# Bank_13_Bank_15_Bank_16.net
KiCad netlist of a schematic drawn in Altium Designer
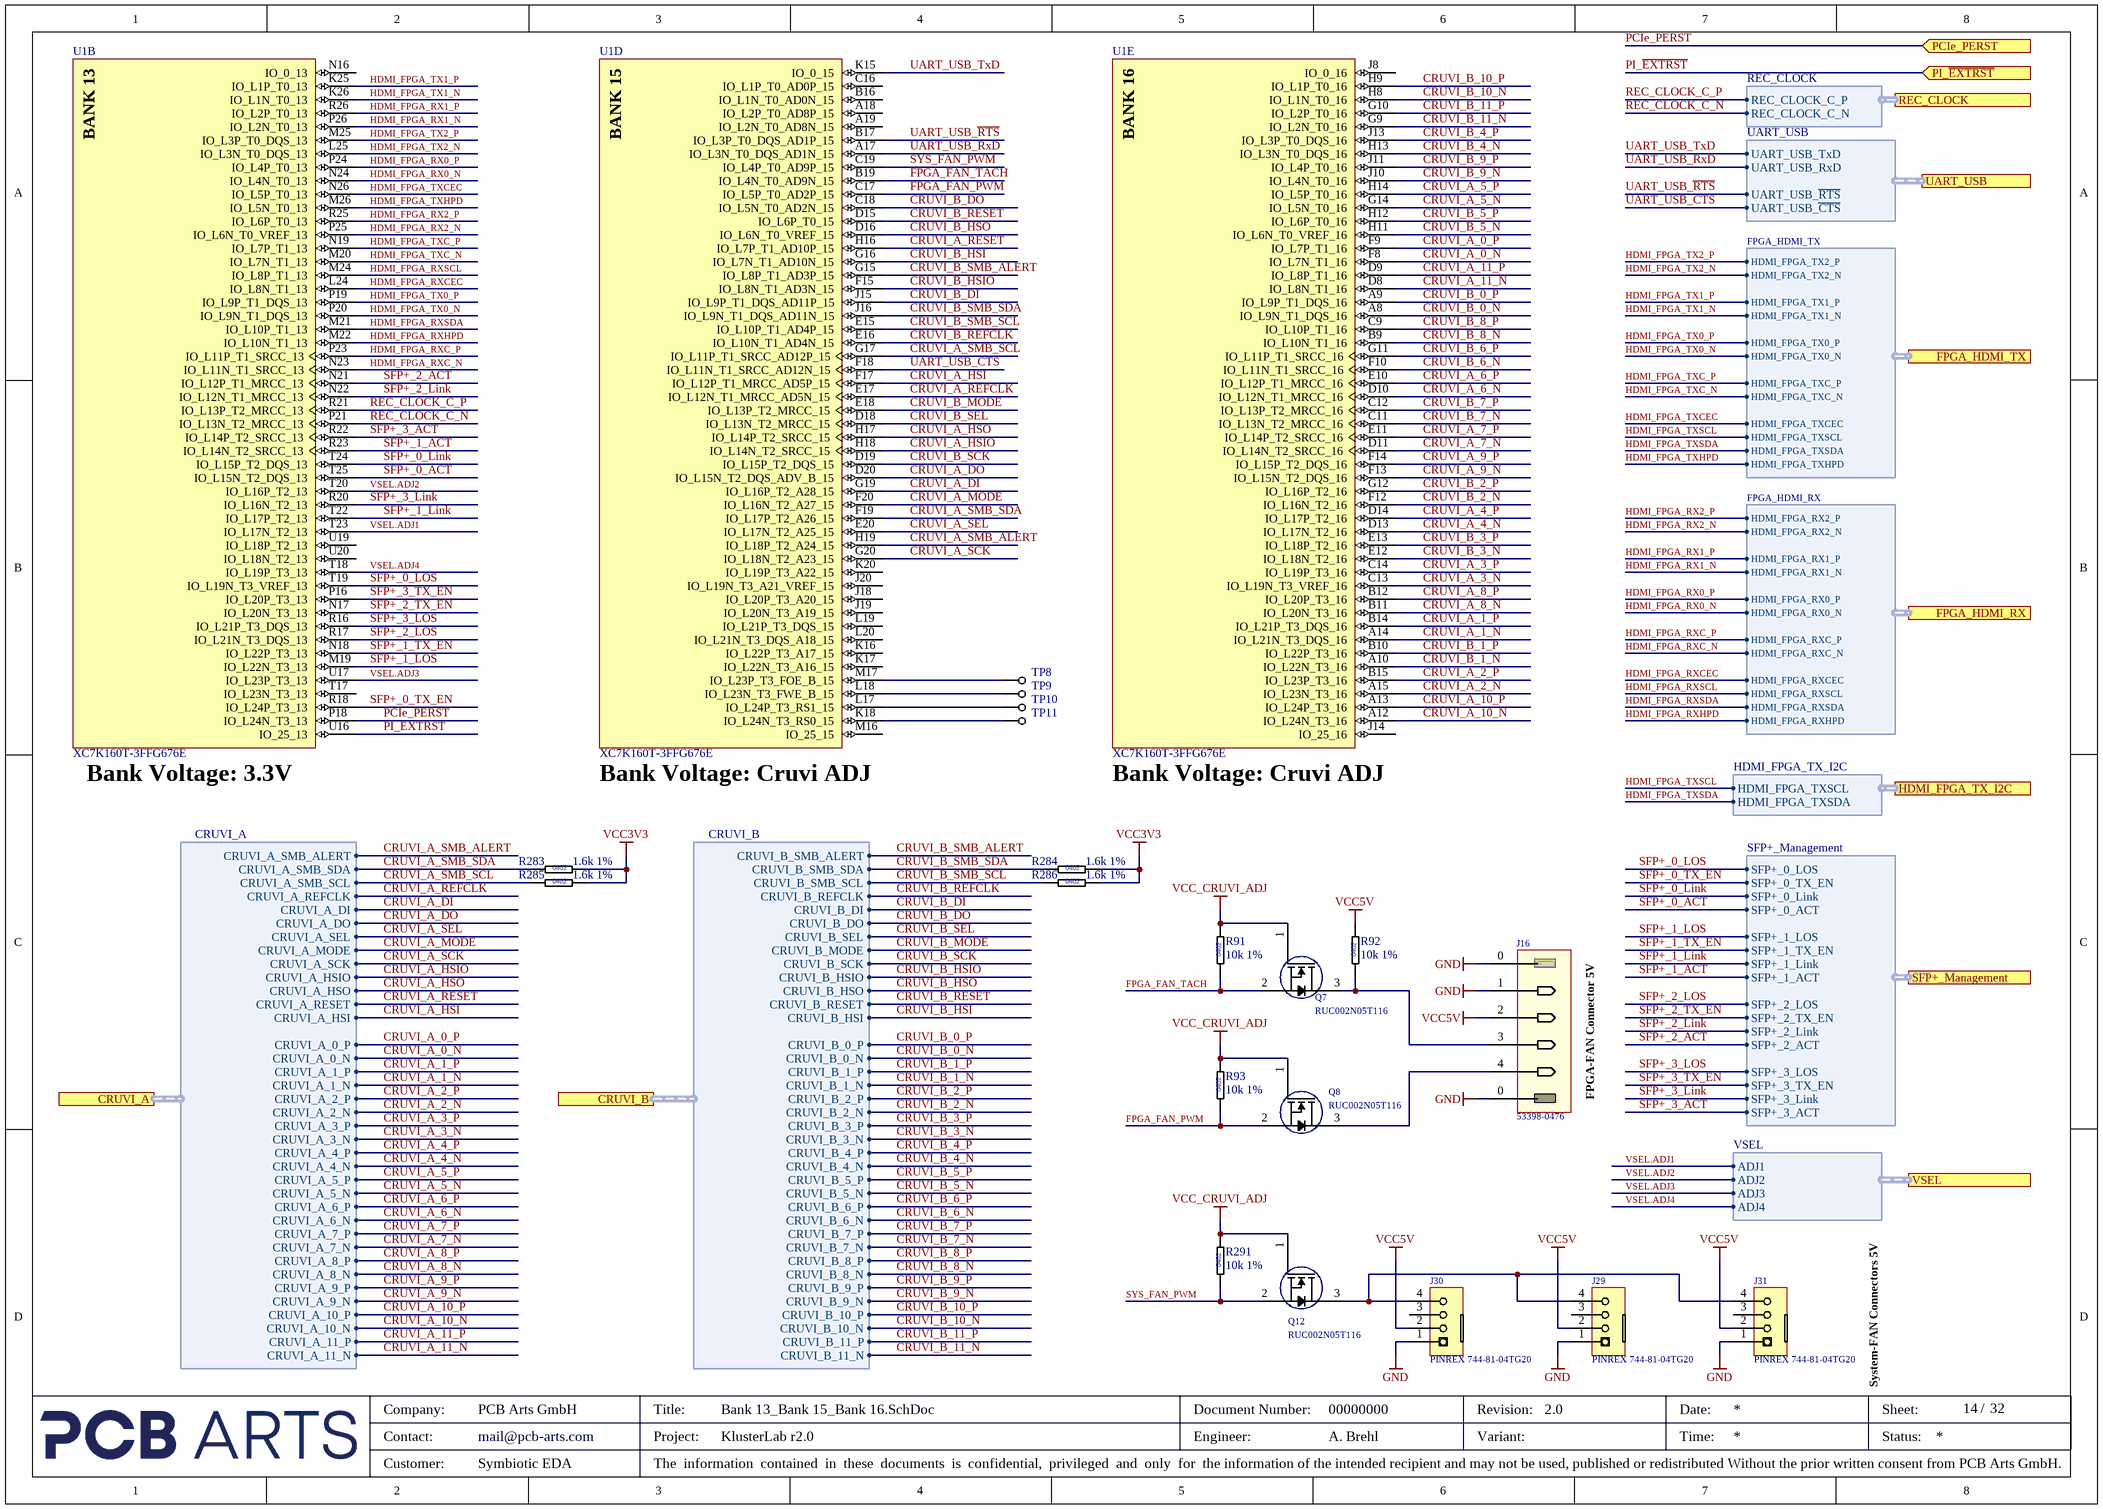
[diagram p0: Bank 13_Bank 15_Bank 16.SchDoc]

(export (version "E")
  (design (tool "Eeschema 10.0.6"))
  (components
    (comp (ref "J16")
      (value "53398-0476")
      (footprint "Conn:Molex 53398-0476")
      (description "1.25mm Pitch, PicoBlade PCB Header, Single Row, horizontal, SMD, 4 Pin")
      (libsource (lib "Conn") (part "53398-0476_1.25mm Pitch, PicoBlade PCB Header, Single Row, horizontal, SMD, 4 Pin"))
    )
    (comp (ref "J29")
      (value "PINREX 744-81-04TG20")
      (footprint "conn:PINREX 744-81-04TG20")
      (description "FAN Connector header 2.54mm 4Pol")
      (libsource (lib "Conn") (part "FAN Connector header 2.54mm 4Pol Pinrex 744-81-04TG20"))
    )
    (comp (ref "J30")
      (value "PINREX 744-81-04TG20")
      (footprint "conn:PINREX 744-81-04TG20")
      (description "FAN Connector header 2.54mm 4Pol")
      (libsource (lib "Conn") (part "FAN Connector header 2.54mm 4Pol Pinrex 744-81-04TG20"))
    )
    (comp (ref "J31")
      (value "PINREX 744-81-04TG20")
      (footprint "conn:PINREX 744-81-04TG20")
      (description "FAN Connector header 2.54mm 4Pol")
      (libsource (lib "Conn") (part "FAN Connector header 2.54mm 4Pol Pinrex 744-81-04TG20"))
    )
    (comp (ref "Q7")
      (value "RUC002N05T116")
      (footprint "trans:SOT95P251X112-3N")
      (description "MOSFET N-Ch 1.2 VGS Spec")
      (libsource (lib "Trans") (part "RUC002N05T116_MOSFET N-Ch 1.2 VGS Spec"))
    )
    (comp (ref "Q8")
      (value "RUC002N05T116")
      (footprint "trans:SOT95P251X112-3N")
      (description "MOSFET N-Ch 1.2 VGS Spec")
      (libsource (lib "Trans") (part "RUC002N05T116_MOSFET N-Ch 1.2 VGS Spec"))
    )
    (comp (ref "Q12")
      (value "RUC002N05T116")
      (footprint "trans:SOT95P251X112-3N")
      (description "MOSFET N-Ch 1.2 VGS Spec")
      (libsource (lib "Trans") (part "RUC002N05T116_MOSFET N-Ch 1.2 VGS Spec"))
    )
    (comp (ref "R91")
      (value "10k 1%")
      (footprint "Res:RES_0402_L")
      (description "Thick Film Resistors - SMD 10kOhm 1%")
      (libsource (lib "Res") (part "RES_0402_10k_1%"))
    )
    (comp (ref "R92")
      (value "10k 1%")
      (footprint "Res:RES_0402_L")
      (description "Thick Film Resistors - SMD 10kOhm 1%")
      (libsource (lib "Res") (part "RES_0402_10k_1%"))
    )
    (comp (ref "R93")
      (value "10k 1%")
      (footprint "Res:RES_0402_L")
      (description "Thick Film Resistors - SMD 10kOhm 1%")
      (libsource (lib "Res") (part "RES_0402_10k_1%"))
    )
    (comp (ref "R283")
      (value "1.6k 1%")
      (footprint "Res:RES_0402_L")
      (description "Thick Film Resistors - SMD 1.6kOhm 1%")
      (libsource (lib "Res") (part "RES_0402_1.6k_1%"))
    )
    (comp (ref "R284")
      (value "1.6k 1%")
      (footprint "Res:RES_0402_L")
      (description "Thick Film Resistors - SMD 1.6kOhm 1%")
      (libsource (lib "Res") (part "RES_0402_1.6k_1%"))
    )
    (comp (ref "R285")
      (value "1.6k 1%")
      (footprint "Res:RES_0402_L")
      (description "Thick Film Resistors - SMD 1.6kOhm 1%")
      (libsource (lib "Res") (part "RES_0402_1.6k_1%"))
    )
    (comp (ref "R286")
      (value "1.6k 1%")
      (footprint "Res:RES_0402_L")
      (description "Thick Film Resistors - SMD 1.6kOhm 1%")
      (libsource (lib "Res") (part "RES_0402_1.6k_1%"))
    )
    (comp (ref "R291")
      (value "10k 1%")
      (footprint "Res:RES_0402_L")
      (description "Thick Film Resistors - SMD 10kOhm 1%")
      (libsource (lib "Res") (part "RES_0402_10k_1%"))
    )
    (comp (ref "TP8")
      (value "Testpoint")
      (footprint "Electro_mech:Testpoint 0.8mm")
      (description "Testpoint 0.8mm")
      (libsource (lib "Electro_Mech") (part "Testpoint 0.8mm"))
    )
    (comp (ref "TP9")
      (value "Testpoint")
      (footprint "Electro_mech:Testpoint 0.8mm")
      (description "Testpoint 0.8mm")
      (libsource (lib "Electro_Mech") (part "Testpoint 0.8mm"))
    )
    (comp (ref "TP10")
      (value "Testpoint")
      (footprint "Electro_mech:Testpoint 0.8mm")
      (description "Testpoint 0.8mm")
      (libsource (lib "Electro_Mech") (part "Testpoint 0.8mm"))
    )
    (comp (ref "TP11")
      (value "Testpoint")
      (footprint "Electro_mech:Testpoint 0.8mm")
      (description "Testpoint 0.8mm")
      (libsource (lib "Electro_Mech") (part "Testpoint 0.8mm"))
    )
    (comp (ref "U1")
      (value "XC7K160T-3FFG676E")
      (footprint "Digital:BGA100P2700X2700X317-676N")
      (description "Kintex-7 FPGA, 400 User I/Os, 8 GTX, 676-Ball BGA, Speed Grade 3, Extended Grade, Pb-Free")
      (libsource (lib "Digital") (part "XC7K160T-3FFG676E_Kintex-7 FPGA, 400 User I/Os, 8 GTX, FFG676"))
    )
  )
  (nets
    (net (code "10") (name "/CRUVI_A_0_N") (class "Default")
      (node (ref "U1") (pin "F8") (pinfunction "IO_L7N_T1_16_F8") (pintype "bidirectional"))
    )
    (net (code "11") (name "/CRUVI_A_0_P") (class "Default")
      (node (ref "U1") (pin "F9") (pinfunction "IO_L7P_T1_16_F9") (pintype "bidirectional"))
    )
    (net (code "12") (name "/CRUVI_A_1_N") (class "Default")
      (node (ref "U1") (pin "A14") (pinfunction "IO_L21N_T3_DQS_16_A14") (pintype "bidirectional"))
    )
    (net (code "13") (name "/CRUVI_A_1_P") (class "Default")
      (node (ref "U1") (pin "B14") (pinfunction "IO_L21P_T3_DQS_16_B14") (pintype "bidirectional"))
    )
    (net (code "14") (name "/CRUVI_A_2_N") (class "Default")
      (node (ref "U1") (pin "A15") (pinfunction "IO_L23N_T3_16_A15") (pintype "bidirectional"))
    )
    (net (code "15") (name "/CRUVI_A_2_P") (class "Default")
      (node (ref "U1") (pin "B15") (pinfunction "IO_L23P_T3_16_B15") (pintype "bidirectional"))
    )
    (net (code "16") (name "/CRUVI_A_3_N") (class "Default")
      (node (ref "U1") (pin "C13") (pinfunction "IO_L19N_T3_VREF_16_C13") (pintype "bidirectional"))
    )
    (net (code "17") (name "/CRUVI_A_3_P") (class "Default")
      (node (ref "U1") (pin "C14") (pinfunction "IO_L19P_T3_16_C14") (pintype "bidirectional"))
    )
    (net (code "18") (name "/CRUVI_A_4_N") (class "Default")
      (node (ref "U1") (pin "D13") (pinfunction "IO_L17N_T2_16_D13") (pintype "bidirectional"))
    )
    (net (code "19") (name "/CRUVI_A_4_P") (class "Default")
      (node (ref "U1") (pin "D14") (pinfunction "IO_L17P_T2_16_D14") (pintype "bidirectional"))
    )
    (net (code "20") (name "/CRUVI_A_5_N") (class "Default")
      (node (ref "U1") (pin "G14") (pinfunction "IO_L5N_T0_16_G14") (pintype "bidirectional"))
    )
    (net (code "21") (name "/CRUVI_A_5_P") (class "Default")
      (node (ref "U1") (pin "H14") (pinfunction "IO_L5P_T0_16_H14") (pintype "bidirectional"))
    )
    (net (code "22") (name "/CRUVI_A_6_N") (class "Default")
      (node (ref "U1") (pin "D10") (pinfunction "IO_L12N_T1_MRCC_16_D10") (pintype "bidirectional"))
    )
    (net (code "23") (name "/CRUVI_A_6_P") (class "Default")
      (node (ref "U1") (pin "E10") (pinfunction "IO_L12P_T1_MRCC_16_E10") (pintype "bidirectional"))
    )
    (net (code "24") (name "/CRUVI_A_7_N") (class "Default")
      (node (ref "U1") (pin "D11") (pinfunction "IO_L14N_T2_SRCC_16_D11") (pintype "bidirectional"))
    )
    (net (code "25") (name "/CRUVI_A_7_P") (class "Default")
      (node (ref "U1") (pin "E11") (pinfunction "IO_L14P_T2_SRCC_16_E11") (pintype "bidirectional"))
    )
    (net (code "26") (name "/CRUVI_A_8_N") (class "Default")
      (node (ref "U1") (pin "B11") (pinfunction "IO_L20N_T3_16_B11") (pintype "bidirectional"))
    )
    (net (code "27") (name "/CRUVI_A_8_P") (class "Default")
      (node (ref "U1") (pin "B12") (pinfunction "IO_L20P_T3_16_B12") (pintype "bidirectional"))
    )
    (net (code "28") (name "/CRUVI_A_9_N") (class "Default")
      (node (ref "U1") (pin "F13") (pinfunction "IO_L15N_T2_DQS_16_F13") (pintype "bidirectional"))
    )
    (net (code "29") (name "/CRUVI_A_9_P") (class "Default")
      (node (ref "U1") (pin "F14") (pinfunction "IO_L15P_T2_DQS_16_F14") (pintype "bidirectional"))
    )
    (net (code "30") (name "/CRUVI_A_10_N") (class "Default")
      (node (ref "U1") (pin "A12") (pinfunction "IO_L24N_T3_16_A12") (pintype "bidirectional"))
    )
    (net (code "31") (name "/CRUVI_A_10_P") (class "Default")
      (node (ref "U1") (pin "A13") (pinfunction "IO_L24P_T3_16_A13") (pintype "bidirectional"))
    )
    (net (code "32") (name "/CRUVI_A_11_N") (class "Default")
      (node (ref "U1") (pin "D8") (pinfunction "IO_L8N_T1_16_D8") (pintype "bidirectional"))
    )
    (net (code "33") (name "/CRUVI_A_11_P") (class "Default")
      (node (ref "U1") (pin "D9") (pinfunction "IO_L8P_T1_16_D9") (pintype "bidirectional"))
    )
    (net (code "34") (name "/CRUVI_A_DI") (class "Default")
      (node (ref "U1") (pin "G19") (pinfunction "IO_L16P_T2_A28_15_G19") (pintype "bidirectional"))
    )
    (net (code "35") (name "/CRUVI_A_DO") (class "Default")
      (node (ref "U1") (pin "D20") (pinfunction "IO_L15N_T2_DQS_ADV_B_15_D20") (pintype "bidirectional"))
    )
    (net (code "36") (name "/CRUVI_A_HSI") (class "Default")
      (node (ref "U1") (pin "F17") (pinfunction "IO_L12P_T1_MRCC_AD5P_15_F17") (pintype "bidirectional"))
    )
    (net (code "37") (name "/CRUVI_A_HSIO") (class "Default")
      (node (ref "U1") (pin "H18") (pinfunction "IO_L14N_T2_SRCC_15_H18") (pintype "bidirectional"))
    )
    (net (code "38") (name "/CRUVI_A_HSO") (class "Default")
      (node (ref "U1") (pin "H17") (pinfunction "IO_L14P_T2_SRCC_15_H17") (pintype "bidirectional"))
    )
    (net (code "39") (name "/CRUVI_A_MODE") (class "Default")
      (node (ref "U1") (pin "F20") (pinfunction "IO_L16N_T2_A27_15_F20") (pintype "bidirectional"))
    )
    (net (code "40") (name "/CRUVI_A_REFCLK") (class "Default")
      (node (ref "U1") (pin "E17") (pinfunction "IO_L12N_T1_MRCC_AD5N_15_E17") (pintype "bidirectional"))
    )
    (net (code "41") (name "/CRUVI_A_RESET") (class "Default")
      (node (ref "U1") (pin "H16") (pinfunction "IO_L7P_T1_AD10P_15_H16") (pintype "bidirectional"))
    )
    (net (code "42") (name "/CRUVI_A_SCK") (class "Default")
      (node (ref "U1") (pin "G20") (pinfunction "IO_L18N_T2_A23_15_G20") (pintype "bidirectional"))
    )
    (net (code "43") (name "/CRUVI_A_SEL") (class "Default")
      (node (ref "U1") (pin "E20") (pinfunction "IO_L17N_T2_A25_15_E20") (pintype "bidirectional"))
    )
    (net (code "44") (name "/CRUVI_A_SMB_ALERT") (class "Default")
      (node (ref "U1") (pin "H19") (pinfunction "IO_L18P_T2_A24_15_H19") (pintype "bidirectional"))
    )
    (net (code "45") (name "/CRUVI_A_SMB_SCL") (class "Default")
      (node (ref "R285") (pin "1") (pinfunction "1_1") (pintype "passive"))
      (node (ref "U1") (pin "G17") (pinfunction "IO_L11P_T1_SRCC_AD12P_15_G17") (pintype "bidirectional"))
    )
    (net (code "46") (name "/CRUVI_A_SMB_SDA") (class "Default")
      (node (ref "R283") (pin "1") (pinfunction "1_1") (pintype "passive"))
      (node (ref "U1") (pin "F19") (pinfunction "IO_L17P_T2_A26_15_F19") (pintype "bidirectional"))
    )
    (net (code "47") (name "/CRUVI_B_0_N") (class "Default")
      (node (ref "U1") (pin "A8") (pinfunction "IO_L9N_T1_DQS_16_A8") (pintype "bidirectional"))
    )
    (net (code "48") (name "/CRUVI_B_0_P") (class "Default")
      (node (ref "U1") (pin "A9") (pinfunction "IO_L9P_T1_DQS_16_A9") (pintype "bidirectional"))
    )
    (net (code "49") (name "/CRUVI_B_1_N") (class "Default")
      (node (ref "U1") (pin "A10") (pinfunction "IO_L22N_T3_16_A10") (pintype "bidirectional"))
    )
    (net (code "50") (name "/CRUVI_B_1_P") (class "Default")
      (node (ref "U1") (pin "B10") (pinfunction "IO_L22P_T3_16_B10") (pintype "bidirectional"))
    )
    (net (code "51") (name "/CRUVI_B_2_N") (class "Default")
      (node (ref "U1") (pin "F12") (pinfunction "IO_L16N_T2_16_F12") (pintype "bidirectional"))
    )
    (net (code "52") (name "/CRUVI_B_2_P") (class "Default")
      (node (ref "U1") (pin "G12") (pinfunction "IO_L16P_T2_16_G12") (pintype "bidirectional"))
    )
    (net (code "53") (name "/CRUVI_B_3_N") (class "Default")
      (node (ref "U1") (pin "E12") (pinfunction "IO_L18N_T2_16_E12") (pintype "bidirectional"))
    )
    (net (code "54") (name "/CRUVI_B_3_P") (class "Default")
      (node (ref "U1") (pin "E13") (pinfunction "IO_L18P_T2_16_E13") (pintype "bidirectional"))
    )
    (net (code "55") (name "/CRUVI_B_4_N") (class "Default")
      (node (ref "U1") (pin "H13") (pinfunction "IO_L3N_T0_DQS_16_H13") (pintype "bidirectional"))
    )
    (net (code "56") (name "/CRUVI_B_4_P") (class "Default")
      (node (ref "U1") (pin "J13") (pinfunction "IO_L3P_T0_DQS_16_J13") (pintype "bidirectional"))
    )
    (net (code "57") (name "/CRUVI_B_5_N") (class "Default")
      (node (ref "U1") (pin "H11") (pinfunction "IO_L6N_T0_VREF_16_H11") (pintype "bidirectional"))
    )
    (net (code "58") (name "/CRUVI_B_5_P") (class "Default")
      (node (ref "U1") (pin "H12") (pinfunction "IO_L6P_T0_16_H12") (pintype "bidirectional"))
    )
    (net (code "59") (name "/CRUVI_B_6_N") (class "Default")
      (node (ref "U1") (pin "F10") (pinfunction "IO_L11N_T1_SRCC_16_F10") (pintype "bidirectional"))
    )
    (net (code "60") (name "/CRUVI_B_6_P") (class "Default")
      (node (ref "U1") (pin "G11") (pinfunction "IO_L11P_T1_SRCC_16_G11") (pintype "bidirectional"))
    )
    (net (code "61") (name "/CRUVI_B_7_N") (class "Default")
      (node (ref "U1") (pin "C11") (pinfunction "IO_L13N_T2_MRCC_16_C11") (pintype "bidirectional"))
    )
    (net (code "62") (name "/CRUVI_B_7_P") (class "Default")
      (node (ref "U1") (pin "C12") (pinfunction "IO_L13P_T2_MRCC_16_C12") (pintype "bidirectional"))
    )
    (net (code "63") (name "/CRUVI_B_8_N") (class "Default")
      (node (ref "U1") (pin "B9") (pinfunction "IO_L10N_T1_16_B9") (pintype "bidirectional"))
    )
    (net (code "64") (name "/CRUVI_B_8_P") (class "Default")
      (node (ref "U1") (pin "C9") (pinfunction "IO_L10P_T1_16_C9") (pintype "bidirectional"))
    )
    (net (code "65") (name "/CRUVI_B_9_N") (class "Default")
      (node (ref "U1") (pin "J10") (pinfunction "IO_L4N_T0_16_J10") (pintype "bidirectional"))
    )
    (net (code "66") (name "/CRUVI_B_9_P") (class "Default")
      (node (ref "U1") (pin "J11") (pinfunction "IO_L4P_T0_16_J11") (pintype "bidirectional"))
    )
    (net (code "67") (name "/CRUVI_B_10_N") (class "Default")
      (node (ref "U1") (pin "H8") (pinfunction "IO_L1N_T0_16_H8") (pintype "bidirectional"))
    )
    (net (code "68") (name "/CRUVI_B_10_P") (class "Default")
      (node (ref "U1") (pin "H9") (pinfunction "IO_L1P_T0_16_H9") (pintype "bidirectional"))
    )
    (net (code "69") (name "/CRUVI_B_11_N") (class "Default")
      (node (ref "U1") (pin "G9") (pinfunction "IO_L2N_T0_16_G9") (pintype "bidirectional"))
    )
    (net (code "70") (name "/CRUVI_B_11_P") (class "Default")
      (node (ref "U1") (pin "G10") (pinfunction "IO_L2P_T0_16_G10") (pintype "bidirectional"))
    )
    (net (code "71") (name "/CRUVI_B_DI") (class "Default")
      (node (ref "U1") (pin "J15") (pinfunction "IO_L9P_T1_DQS_AD11P_15_J15") (pintype "bidirectional"))
    )
    (net (code "72") (name "/CRUVI_B_DO") (class "Default")
      (node (ref "U1") (pin "C18") (pinfunction "IO_L5N_T0_AD2N_15_C18") (pintype "bidirectional"))
    )
    (net (code "73") (name "/CRUVI_B_HSI") (class "Default")
      (node (ref "U1") (pin "G16") (pinfunction "IO_L7N_T1_AD10N_15_G16") (pintype "bidirectional"))
    )
    (net (code "74") (name "/CRUVI_B_HSIO") (class "Default")
      (node (ref "U1") (pin "F15") (pinfunction "IO_L8N_T1_AD3N_15_F15") (pintype "bidirectional"))
    )
    (net (code "75") (name "/CRUVI_B_HSO") (class "Default")
      (node (ref "U1") (pin "D16") (pinfunction "IO_L6N_T0_VREF_15_D16") (pintype "bidirectional"))
    )
    (net (code "76") (name "/CRUVI_B_MODE") (class "Default")
      (node (ref "U1") (pin "E18") (pinfunction "IO_L13P_T2_MRCC_15_E18") (pintype "bidirectional"))
    )
    (net (code "77") (name "/CRUVI_B_REFCLK") (class "Default")
      (node (ref "U1") (pin "E16") (pinfunction "IO_L10N_T1_AD4N_15_E16") (pintype "bidirectional"))
    )
    (net (code "78") (name "/CRUVI_B_RESET") (class "Default")
      (node (ref "U1") (pin "D15") (pinfunction "IO_L6P_T0_15_D15") (pintype "bidirectional"))
    )
    (net (code "79") (name "/CRUVI_B_SCK") (class "Default")
      (node (ref "U1") (pin "D19") (pinfunction "IO_L15P_T2_DQS_15_D19") (pintype "bidirectional"))
    )
    (net (code "80") (name "/CRUVI_B_SEL") (class "Default")
      (node (ref "U1") (pin "D18") (pinfunction "IO_L13N_T2_MRCC_15_D18") (pintype "bidirectional"))
    )
    (net (code "81") (name "/CRUVI_B_SMB_ALERT") (class "Default")
      (node (ref "U1") (pin "G15") (pinfunction "IO_L8P_T1_AD3P_15_G15") (pintype "bidirectional"))
    )
    (net (code "82") (name "/CRUVI_B_SMB_SCL") (class "Default")
      (node (ref "R286") (pin "1") (pinfunction "1_1") (pintype "passive"))
      (node (ref "U1") (pin "E15") (pinfunction "IO_L10P_T1_AD4P_15_E15") (pintype "bidirectional"))
    )
    (net (code "83") (name "/CRUVI_B_SMB_SDA") (class "Default")
      (node (ref "R284") (pin "1") (pinfunction "1_1") (pintype "passive"))
      (node (ref "U1") (pin "J16") (pinfunction "IO_L9N_T1_DQS_AD11N_15_J16") (pintype "bidirectional"))
    )
    (net (code "84") (name "/FPGA_FAN_PWM") (class "Default")
      (node (ref "Q8") (pin "2") (pinfunction "D_2") (pintype "passive"))
      (node (ref "R93") (pin "1") (pinfunction "1_1") (pintype "passive"))
      (node (ref "U1") (pin "C17") (pinfunction "IO_L5P_T0_AD2P_15_C17") (pintype "bidirectional"))
    )
    (net (code "85") (name "/FPGA_FAN_TACH") (class "Default")
      (node (ref "Q7") (pin "2") (pinfunction "D_2") (pintype "passive"))
      (node (ref "R91") (pin "1") (pinfunction "1_1") (pintype "passive"))
      (node (ref "U1") (pin "B19") (pinfunction "IO_L4N_T0_AD9N_15_B19") (pintype "bidirectional"))
    )
    (net (code "86") (name "/HDMI_FPGA_RX0_N") (class "Default")
      (node (ref "U1") (pin "N24") (pinfunction "IO_L4N_T0_13_N24") (pintype "bidirectional"))
    )
    (net (code "87") (name "/HDMI_FPGA_RX0_P") (class "Default")
      (node (ref "U1") (pin "P24") (pinfunction "IO_L4P_T0_13_P24") (pintype "bidirectional"))
    )
    (net (code "88") (name "/HDMI_FPGA_RX1_N") (class "Default")
      (node (ref "U1") (pin "P26") (pinfunction "IO_L2N_T0_13_P26") (pintype "bidirectional"))
    )
    (net (code "89") (name "/HDMI_FPGA_RX1_P") (class "Default")
      (node (ref "U1") (pin "R26") (pinfunction "IO_L2P_T0_13_R26") (pintype "bidirectional"))
    )
    (net (code "90") (name "/HDMI_FPGA_RX2_N") (class "Default")
      (node (ref "U1") (pin "P25") (pinfunction "IO_L6N_T0_VREF_13_P25") (pintype "bidirectional"))
    )
    (net (code "91") (name "/HDMI_FPGA_RX2_P") (class "Default")
      (node (ref "U1") (pin "R25") (pinfunction "IO_L6P_T0_13_R25") (pintype "bidirectional"))
    )
    (net (code "92") (name "/HDMI_FPGA_RXCEC") (class "Default")
      (node (ref "U1") (pin "L24") (pinfunction "IO_L8N_T1_13_L24") (pintype "bidirectional"))
    )
    (net (code "93") (name "/HDMI_FPGA_RXC_N") (class "Default")
      (node (ref "U1") (pin "N23") (pinfunction "IO_L11N_T1_SRCC_13_N23") (pintype "bidirectional"))
    )
    (net (code "94") (name "/HDMI_FPGA_RXC_P") (class "Default")
      (node (ref "U1") (pin "P23") (pinfunction "IO_L11P_T1_SRCC_13_P23") (pintype "bidirectional"))
    )
    (net (code "95") (name "/HDMI_FPGA_RXHPD") (class "Default")
      (node (ref "U1") (pin "M22") (pinfunction "IO_L10N_T1_13_M22") (pintype "bidirectional"))
    )
    (net (code "96") (name "/HDMI_FPGA_RXSCL") (class "Default")
      (node (ref "U1") (pin "M24") (pinfunction "IO_L8P_T1_13_M24") (pintype "bidirectional"))
    )
    (net (code "97") (name "/HDMI_FPGA_RXSDA") (class "Default")
      (node (ref "U1") (pin "M21") (pinfunction "IO_L10P_T1_13_M21") (pintype "bidirectional"))
    )
    (net (code "98") (name "/HDMI_FPGA_TX0_N") (class "Default")
      (node (ref "U1") (pin "P20") (pinfunction "IO_L9N_T1_DQS_13_P20") (pintype "bidirectional"))
    )
    (net (code "99") (name "/HDMI_FPGA_TX0_P") (class "Default")
      (node (ref "U1") (pin "P19") (pinfunction "IO_L9P_T1_DQS_13_P19") (pintype "bidirectional"))
    )
    (net (code "100") (name "/HDMI_FPGA_TX1_N") (class "Default")
      (node (ref "U1") (pin "K26") (pinfunction "IO_L1N_T0_13_K26") (pintype "bidirectional"))
    )
    (net (code "101") (name "/HDMI_FPGA_TX1_P") (class "Default")
      (node (ref "U1") (pin "K25") (pinfunction "IO_L1P_T0_13_K25") (pintype "bidirectional"))
    )
    (net (code "102") (name "/HDMI_FPGA_TX2_N") (class "Default")
      (node (ref "U1") (pin "L25") (pinfunction "IO_L3N_T0_DQS_13_L25") (pintype "bidirectional"))
    )
    (net (code "103") (name "/HDMI_FPGA_TX2_P") (class "Default")
      (node (ref "U1") (pin "M25") (pinfunction "IO_L3P_T0_DQS_13_M25") (pintype "bidirectional"))
    )
    (net (code "104") (name "/HDMI_FPGA_TXCEC") (class "Default")
      (node (ref "U1") (pin "N26") (pinfunction "IO_L5P_T0_13_N26") (pintype "bidirectional"))
    )
    (net (code "105") (name "/HDMI_FPGA_TXC_N") (class "Default")
      (node (ref "U1") (pin "M20") (pinfunction "IO_L7N_T1_13_M20") (pintype "bidirectional"))
    )
    (net (code "106") (name "/HDMI_FPGA_TXC_P") (class "Default")
      (node (ref "U1") (pin "N19") (pinfunction "IO_L7P_T1_13_N19") (pintype "bidirectional"))
    )
    (net (code "107") (name "/HDMI_FPGA_TXHPD") (class "Default")
      (node (ref "U1") (pin "M26") (pinfunction "IO_L5N_T0_13_M26") (pintype "bidirectional"))
    )
    (net (code "110") (name "/PCIe_PERST") (class "Default")
      (node (ref "U1") (pin "P18") (pinfunction "IO_L24N_T3_13_P18") (pintype "bidirectional"))
    )
    (net (code "111") (name "/PI_~{EXTRST}") (class "Default")
      (node (ref "U1") (pin "U16") (pinfunction "IO_25_13_U16") (pintype "bidirectional"))
    )
    (net (code "112") (name "/REC_CLOCK_C_N") (class "Default")
      (node (ref "U1") (pin "P21") (pinfunction "IO_L13N_T2_MRCC_13_P21") (pintype "bidirectional"))
    )
    (net (code "113") (name "/REC_CLOCK_C_P") (class "Default")
      (node (ref "U1") (pin "R21") (pinfunction "IO_L13P_T2_MRCC_13_R21") (pintype "bidirectional"))
    )
    (net (code "114") (name "/SFP+_0_ACT") (class "Default")
      (node (ref "U1") (pin "T25") (pinfunction "IO_L15N_T2_DQS_13_T25") (pintype "bidirectional"))
    )
    (net (code "115") (name "/SFP+_0_LOS") (class "Default")
      (node (ref "U1") (pin "T19") (pinfunction "IO_L19N_T3_VREF_13_T19") (pintype "bidirectional"))
    )
    (net (code "116") (name "/SFP+_0_Link") (class "Default")
      (node (ref "U1") (pin "T24") (pinfunction "IO_L15P_T2_DQS_13_T24") (pintype "bidirectional"))
    )
    (net (code "117") (name "/SFP+_0_TX_EN") (class "Default")
      (node (ref "U1") (pin "R18") (pinfunction "IO_L24P_T3_13_R18") (pintype "bidirectional"))
    )
    (net (code "118") (name "/SFP+_1_ACT") (class "Default")
      (node (ref "U1") (pin "R23") (pinfunction "IO_L14N_T2_SRCC_13_R23") (pintype "bidirectional"))
    )
    (net (code "119") (name "/SFP+_1_LOS") (class "Default")
      (node (ref "U1") (pin "M19") (pinfunction "IO_L22N_T3_13_M19") (pintype "bidirectional"))
    )
    (net (code "120") (name "/SFP+_1_Link") (class "Default")
      (node (ref "U1") (pin "T22") (pinfunction "IO_L17P_T2_13_T22") (pintype "bidirectional"))
    )
    (net (code "121") (name "/SFP+_1_TX_EN") (class "Default")
      (node (ref "U1") (pin "N18") (pinfunction "IO_L22P_T3_13_N18") (pintype "bidirectional"))
    )
    (net (code "122") (name "/SFP+_2_ACT") (class "Default")
      (node (ref "U1") (pin "N21") (pinfunction "IO_L12P_T1_MRCC_13_N21") (pintype "bidirectional"))
    )
    (net (code "123") (name "/SFP+_2_LOS") (class "Default")
      (node (ref "U1") (pin "R17") (pinfunction "IO_L21N_T3_DQS_13_R17") (pintype "bidirectional"))
    )
    (net (code "124") (name "/SFP+_2_Link") (class "Default")
      (node (ref "U1") (pin "N22") (pinfunction "IO_L12N_T1_MRCC_13_N22") (pintype "bidirectional"))
    )
    (net (code "125") (name "/SFP+_2_TX_EN") (class "Default")
      (node (ref "U1") (pin "N17") (pinfunction "IO_L20N_T3_13_N17") (pintype "bidirectional"))
    )
    (net (code "126") (name "/SFP+_3_ACT") (class "Default")
      (node (ref "U1") (pin "R22") (pinfunction "IO_L14P_T2_SRCC_13_R22") (pintype "bidirectional"))
    )
    (net (code "127") (name "/SFP+_3_LOS") (class "Default")
      (node (ref "U1") (pin "R16") (pinfunction "IO_L21P_T3_DQS_13_R16") (pintype "bidirectional"))
    )
    (net (code "128") (name "/SFP+_3_Link") (class "Default")
      (node (ref "U1") (pin "R20") (pinfunction "IO_L16N_T2_13_R20") (pintype "bidirectional"))
    )
    (net (code "129") (name "/SFP+_3_TX_EN") (class "Default")
      (node (ref "U1") (pin "P16") (pinfunction "IO_L20P_T3_13_P16") (pintype "bidirectional"))
    )
    (net (code "130") (name "/SYS_FAN_PWM") (class "Default")
      (node (ref "Q12") (pin "2") (pinfunction "D_2") (pintype "passive"))
      (node (ref "R291") (pin "1") (pinfunction "1_1") (pintype "passive"))
      (node (ref "U1") (pin "C19") (pinfunction "IO_L4P_T0_AD9P_15_C19") (pintype "bidirectional"))
    )
    (net (code "131") (name "/UART_USB_RxD") (class "Default")
      (node (ref "U1") (pin "A17") (pinfunction "IO_L3N_T0_DQS_AD1N_15_A17") (pintype "bidirectional"))
    )
    (net (code "132") (name "/UART_USB_TxD") (class "Default")
      (node (ref "U1") (pin "K15") (pinfunction "IO_0_15_K15") (pintype "bidirectional"))
    )
    (net (code "133") (name "/UART_USB_~{CTS}") (class "Default")
      (node (ref "U1") (pin "F18") (pinfunction "IO_L11N_T1_SRCC_AD12N_15_F18") (pintype "bidirectional"))
    )
    (net (code "134") (name "/UART_USB_~{RTS}") (class "Default")
      (node (ref "U1") (pin "B17") (pinfunction "IO_L3P_T0_DQS_AD1P_15_B17") (pintype "bidirectional"))
    )
    (net (code "135") (name "/VSEL.ADJ1") (class "Default")
      (node (ref "U1") (pin "T23") (pinfunction "IO_L17N_T2_13_T23") (pintype "bidirectional"))
    )
    (net (code "136") (name "/VSEL.ADJ2") (class "Default")
      (node (ref "U1") (pin "T20") (pinfunction "IO_L16P_T2_13_T20") (pintype "bidirectional"))
    )
    (net (code "137") (name "/VSEL.ADJ3") (class "Default")
      (node (ref "U1") (pin "U17") (pinfunction "IO_L23P_T3_13_U17") (pintype "bidirectional"))
    )
    (net (code "138") (name "/VSEL.ADJ4") (class "Default")
      (node (ref "U1") (pin "T18") (pinfunction "IO_L19P_T3_13_T18") (pintype "bidirectional"))
    )
    (net (code "148") (name "GND") (class "Default")
      (node (ref "J16") (pin "0") (pinfunction "0_0") (pintype "passive"))
      (node (ref "J16") (pin "1") (pinfunction "1_1") (pintype "passive"))
      (node (ref "J29") (pin "1") (pinfunction "1_1") (pintype "passive"))
      (node (ref "J30") (pin "1") (pinfunction "1_1") (pintype "passive"))
      (node (ref "J31") (pin "1") (pinfunction "1_1") (pintype "passive"))
    )
    (net (code "149") (name "Net-(Q7-S)") (class "Default")
      (node (ref "J16") (pin "3") (pinfunction "3_3") (pintype "passive"))
      (node (ref "Q7") (pin "3") (pinfunction "S_3") (pintype "passive"))
      (node (ref "R92") (pin "1") (pinfunction "1_1") (pintype "passive"))
    )
    (net (code "150") (name "Net-(Q8-S)") (class "Default")
      (node (ref "J16") (pin "4") (pinfunction "4_4") (pintype "passive"))
      (node (ref "Q8") (pin "3") (pinfunction "S_3") (pintype "passive"))
    )
    (net (code "151") (name "Net-(Q12-S)") (class "Default")
      (node (ref "J29") (pin "4") (pinfunction "4_4") (pintype "passive"))
      (node (ref "J30") (pin "4") (pinfunction "4_4") (pintype "passive"))
      (node (ref "J31") (pin "4") (pinfunction "4_4") (pintype "passive"))
      (node (ref "Q12") (pin "3") (pinfunction "S_3") (pintype "passive"))
    )
    (net (code "152") (name "Net-(TP8-GND)") (class "Default")
      (node (ref "TP8") (pin "1") (pinfunction "GND_1") (pintype "passive"))
      (node (ref "U1") (pin "M17") (pinfunction "IO_L23P_T3_FOE_B_15_M17") (pintype "bidirectional"))
    )
    (net (code "153") (name "Net-(TP9-GND)") (class "Default")
      (node (ref "TP9") (pin "1") (pinfunction "GND_1") (pintype "passive"))
      (node (ref "U1") (pin "L18") (pinfunction "IO_L23N_T3_FWE_B_15_L18") (pintype "bidirectional"))
    )
    (net (code "154") (name "Net-(TP10-GND)") (class "Default")
      (node (ref "TP10") (pin "1") (pinfunction "GND_1") (pintype "passive"))
      (node (ref "U1") (pin "L17") (pinfunction "IO_L24P_T3_RS1_15_L17") (pintype "bidirectional"))
    )
    (net (code "155") (name "Net-(TP11-GND)") (class "Default")
      (node (ref "TP11") (pin "1") (pinfunction "GND_1") (pintype "passive"))
      (node (ref "U1") (pin "K18") (pinfunction "IO_L24N_T3_RS0_15_K18") (pintype "bidirectional"))
    )
    (net (code "156") (name "VCC3V3") (class "Default")
      (node (ref "R283") (pin "2") (pinfunction "2_2") (pintype "passive"))
      (node (ref "R284") (pin "2") (pinfunction "2_2") (pintype "passive"))
      (node (ref "R285") (pin "2") (pinfunction "2_2") (pintype "passive"))
      (node (ref "R286") (pin "2") (pinfunction "2_2") (pintype "passive"))
    )
    (net (code "157") (name "VCC5V") (class "Default")
      (node (ref "J16") (pin "2") (pinfunction "2_2") (pintype "passive"))
      (node (ref "J29") (pin "2") (pinfunction "2_2") (pintype "passive"))
      (node (ref "J30") (pin "2") (pinfunction "2_2") (pintype "passive"))
      (node (ref "J31") (pin "2") (pinfunction "2_2") (pintype "passive"))
      (node (ref "R92") (pin "2") (pinfunction "2_2") (pintype "passive"))
    )
    (net (code "158") (name "VCC_CRUVI_ADJ") (class "Default")
      (node (ref "Q12") (pin "1") (pinfunction "G_1") (pintype "passive"))
      (node (ref "Q7") (pin "1") (pinfunction "G_1") (pintype "passive"))
      (node (ref "Q8") (pin "1") (pinfunction "G_1") (pintype "passive"))
      (node (ref "R291") (pin "2") (pinfunction "2_2") (pintype "passive"))
      (node (ref "R91") (pin "2") (pinfunction "2_2") (pintype "passive"))
      (node (ref "R93") (pin "2") (pinfunction "2_2") (pintype "passive"))
    )
    (net (code "159") (name "unconnected-(J29-Pad3)") (class "Default")
      (node (ref "J29") (pin "3") (pinfunction "3_3") (pintype "passive"))
    )
    (net (code "160") (name "unconnected-(J30-Pad3)") (class "Default")
      (node (ref "J30") (pin "3") (pinfunction "3_3") (pintype "passive"))
    )
    (net (code "161") (name "unconnected-(J31-Pad3)") (class "Default")
      (node (ref "J31") (pin "3") (pinfunction "3_3") (pintype "passive"))
    )
    (net (code "162") (name "unconnected-(U1B-IO_0_13-PadN16)") (class "Default")
      (node (ref "U1") (pin "N16") (pinfunction "IO_0_13_N16") (pintype "bidirectional"))
    )
    (net (code "163") (name "unconnected-(U1B-IO_L18N_T2_13-PadU20)") (class "Default")
      (node (ref "U1") (pin "U20") (pinfunction "IO_L18N_T2_13_U20") (pintype "bidirectional"))
    )
    (net (code "164") (name "unconnected-(U1B-IO_L18P_T2_13-PadU19)") (class "Default")
      (node (ref "U1") (pin "U19") (pinfunction "IO_L18P_T2_13_U19") (pintype "bidirectional"))
    )
    (net (code "165") (name "unconnected-(U1B-IO_L23N_T3_13-PadT17)") (class "Default")
      (node (ref "U1") (pin "T17") (pinfunction "IO_L23N_T3_13_T17") (pintype "bidirectional"))
    )
    (net (code "166") (name "unconnected-(U1D-IO_25_15-PadM16)") (class "Default")
      (node (ref "U1") (pin "M16") (pinfunction "IO_25_15_M16") (pintype "bidirectional"))
    )
    (net (code "167") (name "unconnected-(U1D-IO_L1N_T0_AD0N_15-PadB16)") (class "Default")
      (node (ref "U1") (pin "B16") (pinfunction "IO_L1N_T0_AD0N_15_B16") (pintype "bidirectional"))
    )
    (net (code "168") (name "unconnected-(U1D-IO_L1P_T0_AD0P_15-PadC16)") (class "Default")
      (node (ref "U1") (pin "C16") (pinfunction "IO_L1P_T0_AD0P_15_C16") (pintype "bidirectional"))
    )
    (net (code "169") (name "unconnected-(U1D-IO_L2N_T0_AD8N_15-PadA19)") (class "Default")
      (node (ref "U1") (pin "A19") (pinfunction "IO_L2N_T0_AD8N_15_A19") (pintype "bidirectional"))
    )
    (net (code "170") (name "unconnected-(U1D-IO_L2P_T0_AD8P_15-PadA18)") (class "Default")
      (node (ref "U1") (pin "A18") (pinfunction "IO_L2P_T0_AD8P_15_A18") (pintype "bidirectional"))
    )
    (net (code "171") (name "unconnected-(U1D-IO_L19N_T3_A21_VREF_15-PadJ20)") (class "Default")
      (node (ref "U1") (pin "J20") (pinfunction "IO_L19N_T3_A21_VREF_15_J20") (pintype "bidirectional"))
    )
    (net (code "172") (name "unconnected-(U1D-IO_L19P_T3_A22_15-PadK20)") (class "Default")
      (node (ref "U1") (pin "K20") (pinfunction "IO_L19P_T3_A22_15_K20") (pintype "bidirectional"))
    )
    (net (code "173") (name "unconnected-(U1D-IO_L20N_T3_A19_15-PadJ19)") (class "Default")
      (node (ref "U1") (pin "J19") (pinfunction "IO_L20N_T3_A19_15_J19") (pintype "bidirectional"))
    )
    (net (code "174") (name "unconnected-(U1D-IO_L20P_T3_A20_15-PadJ18)") (class "Default")
      (node (ref "U1") (pin "J18") (pinfunction "IO_L20P_T3_A20_15_J18") (pintype "bidirectional"))
    )
    (net (code "175") (name "unconnected-(U1D-IO_L21N_T3_DQS_A18_15-PadL20)") (class "Default")
      (node (ref "U1") (pin "L20") (pinfunction "IO_L21N_T3_DQS_A18_15_L20") (pintype "bidirectional"))
    )
    (net (code "176") (name "unconnected-(U1D-IO_L21P_T3_DQS_15-PadL19)") (class "Default")
      (node (ref "U1") (pin "L19") (pinfunction "IO_L21P_T3_DQS_15_L19") (pintype "bidirectional"))
    )
    (net (code "177") (name "unconnected-(U1D-IO_L22N_T3_A16_15-PadK17)") (class "Default")
      (node (ref "U1") (pin "K17") (pinfunction "IO_L22N_T3_A16_15_K17") (pintype "bidirectional"))
    )
    (net (code "178") (name "unconnected-(U1D-IO_L22P_T3_A17_15-PadK16)") (class "Default")
      (node (ref "U1") (pin "K16") (pinfunction "IO_L22P_T3_A17_15_K16") (pintype "bidirectional"))
    )
    (net (code "179") (name "unconnected-(U1E-IO_0_16-PadJ8)") (class "Default")
      (node (ref "U1") (pin "J8") (pinfunction "IO_0_16_J8") (pintype "bidirectional"))
    )
    (net (code "180") (name "unconnected-(U1E-IO_25_16-PadJ14)") (class "Default")
      (node (ref "U1") (pin "J14") (pinfunction "IO_25_16_J14") (pintype "bidirectional"))
    )
  )
)
